# xerc2.net
KiCad netlist of a schematic drawn in EAGLE
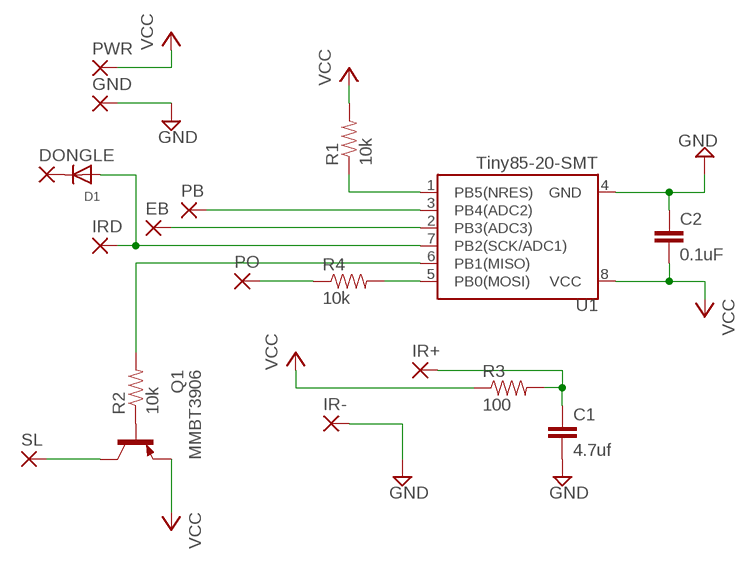
[diagram p0: schematic, sheet 1]

(export (version "E")
  (design (tool "Eeschema 10.0.6"))
  (components
    (comp (ref "C1")
      (value "4.7uf")
      (footprint "eagle-import:0603-CAP")
      (libsource (lib "eagle-import") (part "CAP0603-CAP"))
    )
    (comp (ref "C2")
      (value "0.1uF")
      (footprint "eagle-import:0603-CAP")
      (libsource (lib "eagle-import") (part "0.1UF-25V(+80/-20%)(0603)"))
    )
    (comp (ref "D1")
      (value "DIODESOD-323F")
      (footprint "eagle-import:SOD-323F")
      (libsource (lib "eagle-import") (part "DIODESOD-323F"))
    )
    (comp (ref "DONGLE")
      (value "SMD5")
      (footprint "eagle-import:SMD2,54-5,08")
      (libsource (lib "eagle-import") (part "SMD5"))
    )
    (comp (ref "EB")
      (value "SMD5")
      (footprint "eagle-import:SMD2,54-5,08")
      (libsource (lib "eagle-import") (part "SMD5"))
    )
    (comp (ref "GND")
      (value "SMD5")
      (footprint "eagle-import:SMD2,54-5,08")
      (libsource (lib "eagle-import") (part "SMD5"))
    )
    (comp (ref "IR+")
      (value "SMD5")
      (footprint "eagle-import:SMD2,54-5,08")
      (libsource (lib "eagle-import") (part "SMD5"))
    )
    (comp (ref "IR-")
      (value "SMD5")
      (footprint "eagle-import:SMD2,54-5,08")
      (libsource (lib "eagle-import") (part "SMD5"))
    )
    (comp (ref "IRD")
      (value "SMD5")
      (footprint "eagle-import:SMD2,54-5,08")
      (libsource (lib "eagle-import") (part "SMD5"))
    )
    (comp (ref "MMBT3906")
      (value "Q1")
      (footprint "eagle-import:SOT23")
      (libsource (lib "eagle-import") (part "-?SOT23MMBTA56"))
    )
    (comp (ref "PB")
      (value "SMD5")
      (footprint "eagle-import:SMD2,54-5,08")
      (libsource (lib "eagle-import") (part "SMD5"))
    )
    (comp (ref "PO")
      (value "SMD5")
      (footprint "eagle-import:SMD2,54-5,08")
      (libsource (lib "eagle-import") (part "SMD5"))
    )
    (comp (ref "PWR")
      (value "SMD5")
      (footprint "eagle-import:SMD2,54-5,08")
      (libsource (lib "eagle-import") (part "SMD5"))
    )
    (comp (ref "R1")
      (value "10k")
      (footprint "eagle-import:0603-RES")
      (libsource (lib "eagle-import") (part "RESISTOR0603"))
    )
    (comp (ref "R2")
      (value "10k")
      (footprint "eagle-import:0603-RES")
      (libsource (lib "eagle-import") (part "RESISTOR0603-RES"))
    )
    (comp (ref "R3")
      (value "100")
      (footprint "eagle-import:0603-RES")
      (libsource (lib "eagle-import") (part "RESISTOR0603"))
    )
    (comp (ref "R4")
      (value "10k")
      (footprint "eagle-import:0603-RES")
      (libsource (lib "eagle-import") (part "RESISTOR0603-RES"))
    )
    (comp (ref "SL")
      (value "SMD5")
      (footprint "eagle-import:SMD2,54-5,08")
      (libsource (lib "eagle-import") (part "SMD5"))
    )
    (comp (ref "U1")
      (value "Tiny85-20-SMT")
      (footprint "eagle-import:SO08-EIAJ")
      (libsource (lib "eagle-import") (part "ATTINY45TINY85-20-SMT"))
    )
  )
  (nets
    (net (code "1") (name "GND") (class "Default")
      (node (ref "C1") (pin "2") (pinfunction "2_2") (pintype "passive"))
      (node (ref "C2") (pin "1") (pinfunction "1_1") (pintype "passive"))
      (node (ref "GND") (pin "1") (pinfunction "P_1") (pintype "passive"))
      (node (ref "IR-") (pin "1") (pinfunction "P_1") (pintype "passive"))
      (node (ref "U1") (pin "4") (pinfunction "GND_4") (pintype "bidirectional"))
    )
    (net (code "2") (name "Net-(DONGLE-P)") (class "Default")
      (node (ref "D1") (pin "C") (pinfunction "C_C") (pintype "passive"))
      (node (ref "DONGLE") (pin "1") (pinfunction "P_1") (pintype "passive"))
    )
    (net (code "3") (name "Net-(EB-P)") (class "Default")
      (node (ref "EB") (pin "1") (pinfunction "P_1") (pintype "passive"))
      (node (ref "U1") (pin "2") (pinfunction "PB3(ADC3)_2") (pintype "bidirectional"))
    )
    (net (code "4") (name "Net-(IR+-P)") (class "Default")
      (node (ref "C1") (pin "1") (pinfunction "1_1") (pintype "passive"))
      (node (ref "IR+") (pin "1") (pinfunction "P_1") (pintype "passive"))
      (node (ref "R3") (pin "2") (pinfunction "2_2") (pintype "passive"))
    )
    (net (code "5") (name "Net-(IRD-P)") (class "Default")
      (node (ref "D1") (pin "A") (pinfunction "A_A") (pintype "passive"))
      (node (ref "IRD") (pin "1") (pinfunction "P_1") (pintype "passive"))
      (node (ref "U1") (pin "7") (pinfunction "PB2(SCK/ADC1)_7") (pintype "bidirectional"))
    )
    (net (code "6") (name "Net-(MMBT3906-B)") (class "Default")
      (node (ref "MMBT3906") (pin "1") (pinfunction "B_1") (pintype "passive"))
      (node (ref "R2") (pin "1") (pinfunction "1_1") (pintype "passive"))
    )
    (net (code "7") (name "Net-(MMBT3906-C)") (class "Default")
      (node (ref "MMBT3906") (pin "3") (pinfunction "C_3") (pintype "passive"))
      (node (ref "SL") (pin "1") (pinfunction "P_1") (pintype "passive"))
    )
    (net (code "8") (name "Net-(PB-P)") (class "Default")
      (node (ref "PB") (pin "1") (pinfunction "P_1") (pintype "passive"))
      (node (ref "U1") (pin "3") (pinfunction "PB4(ADC2)_3") (pintype "bidirectional"))
    )
    (net (code "9") (name "Net-(PO-P)") (class "Default")
      (node (ref "PO") (pin "1") (pinfunction "P_1") (pintype "passive"))
      (node (ref "R4") (pin "1") (pinfunction "1_1") (pintype "passive"))
    )
    (net (code "10") (name "Net-(U1-PB0(MOSI))") (class "Default")
      (node (ref "R4") (pin "2") (pinfunction "2_2") (pintype "passive"))
      (node (ref "U1") (pin "5") (pinfunction "PB0(MOSI)_5") (pintype "bidirectional"))
    )
    (net (code "11") (name "Net-(U1-PB1(MISO))") (class "Default")
      (node (ref "R2") (pin "2") (pinfunction "2_2") (pintype "passive"))
      (node (ref "U1") (pin "6") (pinfunction "PB1(MISO)_6") (pintype "bidirectional"))
    )
    (net (code "12") (name "Net-(U1-PB5(NRES))") (class "Default")
      (node (ref "R1") (pin "1") (pinfunction "1_1") (pintype "passive"))
      (node (ref "U1") (pin "1") (pinfunction "PB5(NRES)_1") (pintype "bidirectional"))
    )
    (net (code "13") (name "VCC") (class "Default")
      (node (ref "C2") (pin "2") (pinfunction "2_2") (pintype "passive"))
      (node (ref "MMBT3906") (pin "2") (pinfunction "E_2") (pintype "passive"))
      (node (ref "PWR") (pin "1") (pinfunction "P_1") (pintype "passive"))
      (node (ref "R1") (pin "2") (pinfunction "2_2") (pintype "passive"))
      (node (ref "R3") (pin "1") (pinfunction "1_1") (pintype "passive"))
      (node (ref "U1") (pin "8") (pinfunction "VCC_8") (pintype "bidirectional"))
    )
  )
)
